# michisLamps.net
KiCad netlist of a schematic drawn in EAGLE
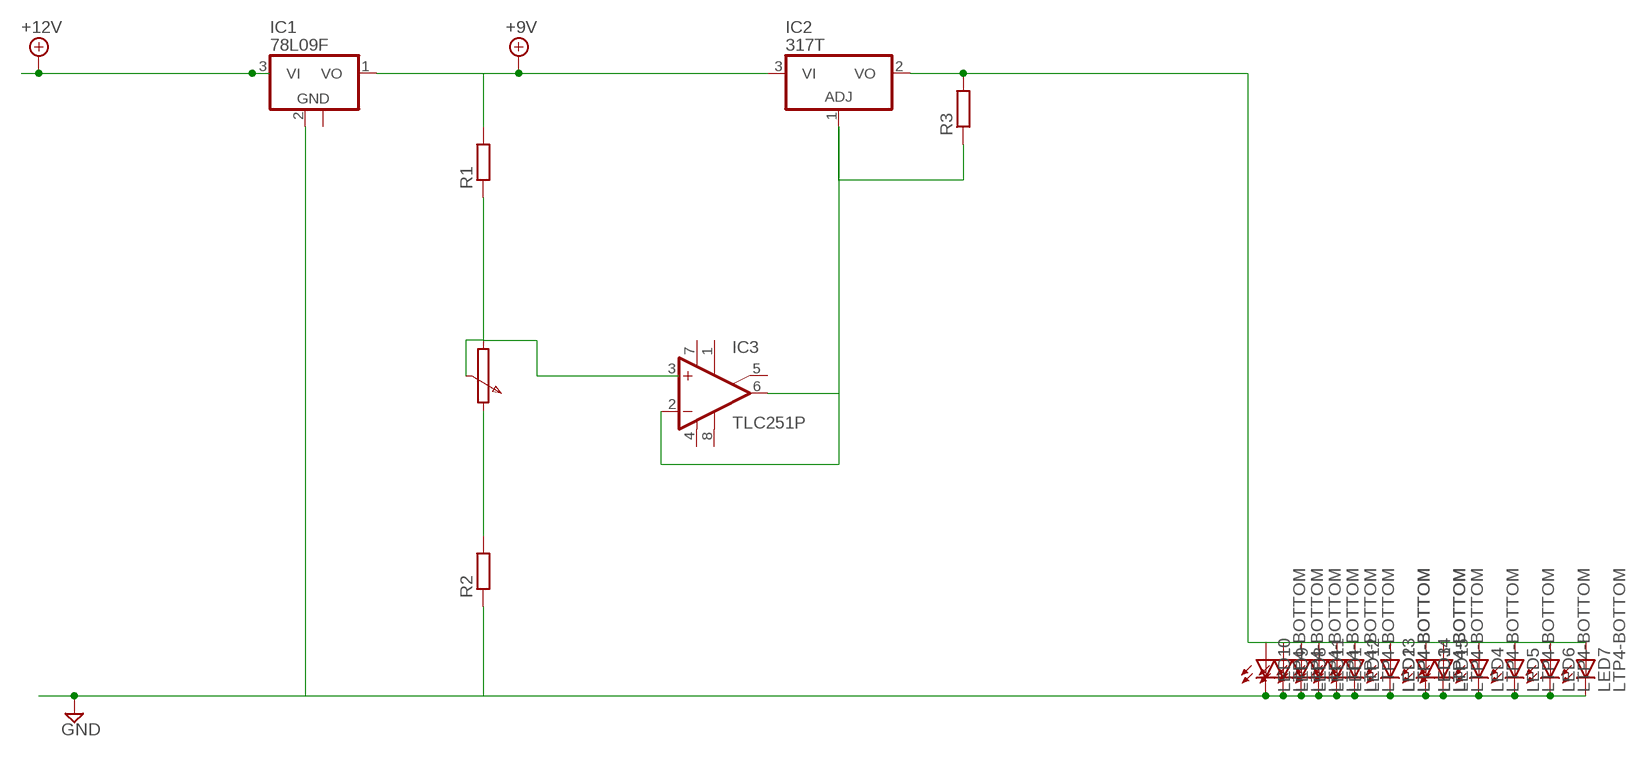
[diagram p0: schematic, sheet 1]

(export (version "E")
  (design (tool "Eeschema 10.0.6"))
  (components
    (comp (ref "IC1")
      (value "78L09F")
      (footprint "eagle-import:SOT89")
      (libsource (lib "eagle-import") (part "78LF09"))
    )
    (comp (ref "IC2")
      (value "317T")
      (footprint "eagle-import:TO220H")
      (libsource (lib "eagle-import") (part "317T"))
    )
    (comp (ref "IC3")
      (value "TLC251P")
      (footprint "eagle-import:DIL08")
      (libsource (lib "eagle-import") (part "TLC251P"))
    )
    (comp (ref "LED1")
      (value "LTP4-BOTTOM")
      (footprint "eagle-import:P47F-BOTTOM")
      (libsource (lib "eagle-import") (part "P4-BOTTOMLT"))
    )
    (comp (ref "LED2")
      (value "LTP4-BOTTOM")
      (footprint "eagle-import:P47F-BOTTOM")
      (libsource (lib "eagle-import") (part "P4-BOTTOMLT"))
    )
    (comp (ref "LED3")
      (value "LTP4-BOTTOM")
      (footprint "eagle-import:P47F-BOTTOM")
      (libsource (lib "eagle-import") (part "P4-BOTTOMLT"))
    )
    (comp (ref "LED4")
      (value "LTP4-BOTTOM")
      (footprint "eagle-import:P47F-BOTTOM")
      (libsource (lib "eagle-import") (part "P4-BOTTOMLT"))
    )
    (comp (ref "LED5")
      (value "LTP4-BOTTOM")
      (footprint "eagle-import:P47F-BOTTOM")
      (libsource (lib "eagle-import") (part "P4-BOTTOMLT"))
    )
    (comp (ref "LED6")
      (value "LTP4-BOTTOM")
      (footprint "eagle-import:P47F-BOTTOM")
      (libsource (lib "eagle-import") (part "P4-BOTTOMLT"))
    )
    (comp (ref "LED7")
      (value "LTP4-BOTTOM")
      (footprint "eagle-import:P47F-BOTTOM")
      (libsource (lib "eagle-import") (part "P4-BOTTOMLT"))
    )
    (comp (ref "LED8")
      (value "LTP4-BOTTOM")
      (footprint "eagle-import:P47F-BOTTOM")
      (libsource (lib "eagle-import") (part "P4-BOTTOMLT"))
    )
    (comp (ref "LED9")
      (value "LTP4-BOTTOM")
      (footprint "eagle-import:P47F-BOTTOM")
      (libsource (lib "eagle-import") (part "P4-BOTTOMLT"))
    )
    (comp (ref "LED10")
      (value "LTP4-BOTTOM")
      (footprint "eagle-import:P47F-BOTTOM")
      (libsource (lib "eagle-import") (part "P4-BOTTOMLT"))
    )
    (comp (ref "LED11")
      (value "LTP4-BOTTOM")
      (footprint "eagle-import:P47F-BOTTOM")
      (libsource (lib "eagle-import") (part "P4-BOTTOMLT"))
    )
    (comp (ref "LED12")
      (value "LTP4-BOTTOM")
      (footprint "eagle-import:P47F-BOTTOM")
      (libsource (lib "eagle-import") (part "P4-BOTTOMLT"))
    )
    (comp (ref "LED13")
      (value "LTP4-BOTTOM")
      (footprint "eagle-import:P47F-BOTTOM")
      (libsource (lib "eagle-import") (part "P4-BOTTOMLT"))
    )
    (comp (ref "LED14")
      (value "LTP4-BOTTOM")
      (footprint "eagle-import:P47F-BOTTOM")
      (libsource (lib "eagle-import") (part "P4-BOTTOMLT"))
    )
    (comp (ref "LED15")
      (value "LTP4-BOTTOM")
      (footprint "eagle-import:P47F-BOTTOM")
      (libsource (lib "eagle-import") (part "P4-BOTTOMLT"))
    )
    (comp (ref "R1")
      (value "R-EU_0207/12")
      (footprint "eagle-import:0207_12")
      (libsource (lib "eagle-import") (part "R-EU_0207/12"))
    )
    (comp (ref "R2")
      (value "R-EU_0207/12")
      (footprint "eagle-import:0207_12")
      (libsource (lib "eagle-import") (part "R-EU_0207/12"))
    )
    (comp (ref "R3")
      (value "R-EU_0207/12")
      (footprint "eagle-import:0207_12")
      (libsource (lib "eagle-import") (part "R-EU_0207/12"))
    )
  )
  (nets
    (net (code "1") (name "+9V") (class "Default")
      (node (ref "IC1") (pin "1") (pinfunction "VO_1") (pintype "passive"))
      (node (ref "IC2") (pin "3") (pinfunction "VI_3") (pintype "input"))
      (node (ref "R1") (pin "2") (pinfunction "2_2") (pintype "passive"))
    )
    (net (code "2") (name "+12V") (class "Default")
      (node (ref "IC1") (pin "3") (pinfunction "VI_3") (pintype "input"))
    )
    (net (code "3") (name "/V+") (class "Default")
      (node (ref "IC3") (pin "7") (pinfunction "V+_7") (pintype "power_in"))
    )
    (net (code "4") (name "/V-") (class "Default")
      (node (ref "IC3") (pin "4") (pinfunction "V-_4") (pintype "power_in"))
    )
    (net (code "5") (name "GND") (class "Default")
      (node (ref "IC1") (pin "2") (pinfunction "GND_2") (pintype "passive"))
      (node (ref "LED1") (pin "C") (pinfunction "C_C") (pintype "passive"))
      (node (ref "LED10") (pin "C") (pinfunction "C_C") (pintype "passive"))
      (node (ref "LED11") (pin "C") (pinfunction "C_C") (pintype "passive"))
      (node (ref "LED12") (pin "C") (pinfunction "C_C") (pintype "passive"))
      (node (ref "LED13") (pin "C") (pinfunction "C_C") (pintype "passive"))
      (node (ref "LED14") (pin "C") (pinfunction "C_C") (pintype "passive"))
      (node (ref "LED15") (pin "C") (pinfunction "C_C") (pintype "passive"))
      (node (ref "LED2") (pin "C") (pinfunction "C_C") (pintype "passive"))
      (node (ref "LED3") (pin "C") (pinfunction "C_C") (pintype "passive"))
      (node (ref "LED4") (pin "C") (pinfunction "C_C") (pintype "passive"))
      (node (ref "LED5") (pin "C") (pinfunction "C_C") (pintype "passive"))
      (node (ref "LED6") (pin "C") (pinfunction "C_C") (pintype "passive"))
      (node (ref "LED7") (pin "C") (pinfunction "C_C") (pintype "passive"))
      (node (ref "LED8") (pin "C") (pinfunction "C_C") (pintype "passive"))
      (node (ref "LED9") (pin "C") (pinfunction "C_C") (pintype "passive"))
      (node (ref "R2") (pin "1") (pinfunction "1_1") (pintype "passive"))
    )
    (net (code "6") (name "Net-(IC2-ADJ)") (class "Default")
      (node (ref "IC2") (pin "1") (pinfunction "ADJ_1") (pintype "input"))
      (node (ref "IC3") (pin "2") (pinfunction "-IN_2") (pintype "input"))
      (node (ref "IC3") (pin "6") (pinfunction "OUT_6") (pintype "output"))
      (node (ref "R3") (pin "1") (pinfunction "1_1") (pintype "passive"))
    )
    (net (code "7") (name "Net-(IC2-VO)") (class "Default")
      (node (ref "IC2") (pin "2") (pinfunction "VO_2") (pintype "passive"))
      (node (ref "LED7") (pin "A") (pinfunction "A_A") (pintype "passive"))
      (node (ref "R3") (pin "2") (pinfunction "2_2") (pintype "passive"))
    )
    (net (code "8") (name "Net-(LED13-PadA)") (class "Default")
      (node (ref "LED13") (pin "A") (pinfunction "A_A") (pintype "passive"))
      (node (ref "LED2") (pin "A") (pinfunction "A_A") (pintype "passive"))
    )
    (net (code "9") (name "Net-(LED14-PadA)") (class "Default")
      (node (ref "LED14") (pin "A") (pinfunction "A_A") (pintype "passive"))
      (node (ref "LED3") (pin "A") (pinfunction "A_A") (pintype "passive"))
    )
    (net (code "10") (name "unconnected-(IC1-GND-Pad2@1)") (class "Default")
      (node (ref "IC1") (pin "2@1") (pinfunction "GND_2@1") (pintype "passive"))
    )
    (net (code "11") (name "unconnected-(IC3-+IN-Pad3)") (class "Default")
      (node (ref "IC3") (pin "3") (pinfunction "+IN_3") (pintype "input"))
    )
    (net (code "12") (name "unconnected-(IC3-ON1-Pad1)") (class "Default")
      (node (ref "IC3") (pin "1") (pinfunction "ON1_1") (pintype "passive"))
    )
    (net (code "13") (name "unconnected-(IC3-ON2-Pad5)") (class "Default")
      (node (ref "IC3") (pin "5") (pinfunction "ON2_5") (pintype "passive"))
    )
    (net (code "14") (name "unconnected-(IC3-OPT-Pad8)") (class "Default")
      (node (ref "IC3") (pin "8") (pinfunction "OPT_8") (pintype "passive"))
    )
    (net (code "15") (name "unconnected-(LED1-PadA)") (class "Default")
      (node (ref "LED1") (pin "A") (pinfunction "A_A") (pintype "passive"))
    )
    (net (code "16") (name "unconnected-(LED4-PadA)") (class "Default")
      (node (ref "LED4") (pin "A") (pinfunction "A_A") (pintype "passive"))
    )
    (net (code "17") (name "unconnected-(LED5-PadA)") (class "Default")
      (node (ref "LED5") (pin "A") (pinfunction "A_A") (pintype "passive"))
    )
    (net (code "18") (name "unconnected-(LED6-PadA)") (class "Default")
      (node (ref "LED6") (pin "A") (pinfunction "A_A") (pintype "passive"))
    )
    (net (code "19") (name "unconnected-(LED8-PadA)") (class "Default")
      (node (ref "LED8") (pin "A") (pinfunction "A_A") (pintype "passive"))
    )
    (net (code "20") (name "unconnected-(LED9-PadA)") (class "Default")
      (node (ref "LED9") (pin "A") (pinfunction "A_A") (pintype "passive"))
    )
    (net (code "21") (name "unconnected-(LED10-PadA)") (class "Default")
      (node (ref "LED10") (pin "A") (pinfunction "A_A") (pintype "passive"))
    )
    (net (code "22") (name "unconnected-(LED11-PadA)") (class "Default")
      (node (ref "LED11") (pin "A") (pinfunction "A_A") (pintype "passive"))
    )
    (net (code "23") (name "unconnected-(LED12-PadA)") (class "Default")
      (node (ref "LED12") (pin "A") (pinfunction "A_A") (pintype "passive"))
    )
    (net (code "24") (name "unconnected-(LED15-PadA)") (class "Default")
      (node (ref "LED15") (pin "A") (pinfunction "A_A") (pintype "passive"))
    )
    (net (code "25") (name "unconnected-(R1-Pad1)") (class "Default")
      (node (ref "R1") (pin "1") (pinfunction "1_1") (pintype "passive"))
    )
    (net (code "26") (name "unconnected-(R2-Pad2)") (class "Default")
      (node (ref "R2") (pin "2") (pinfunction "2_2") (pintype "passive"))
    )
  )
)
